# Relay_Cape.net
KiCad netlist of a schematic drawn in EAGLE
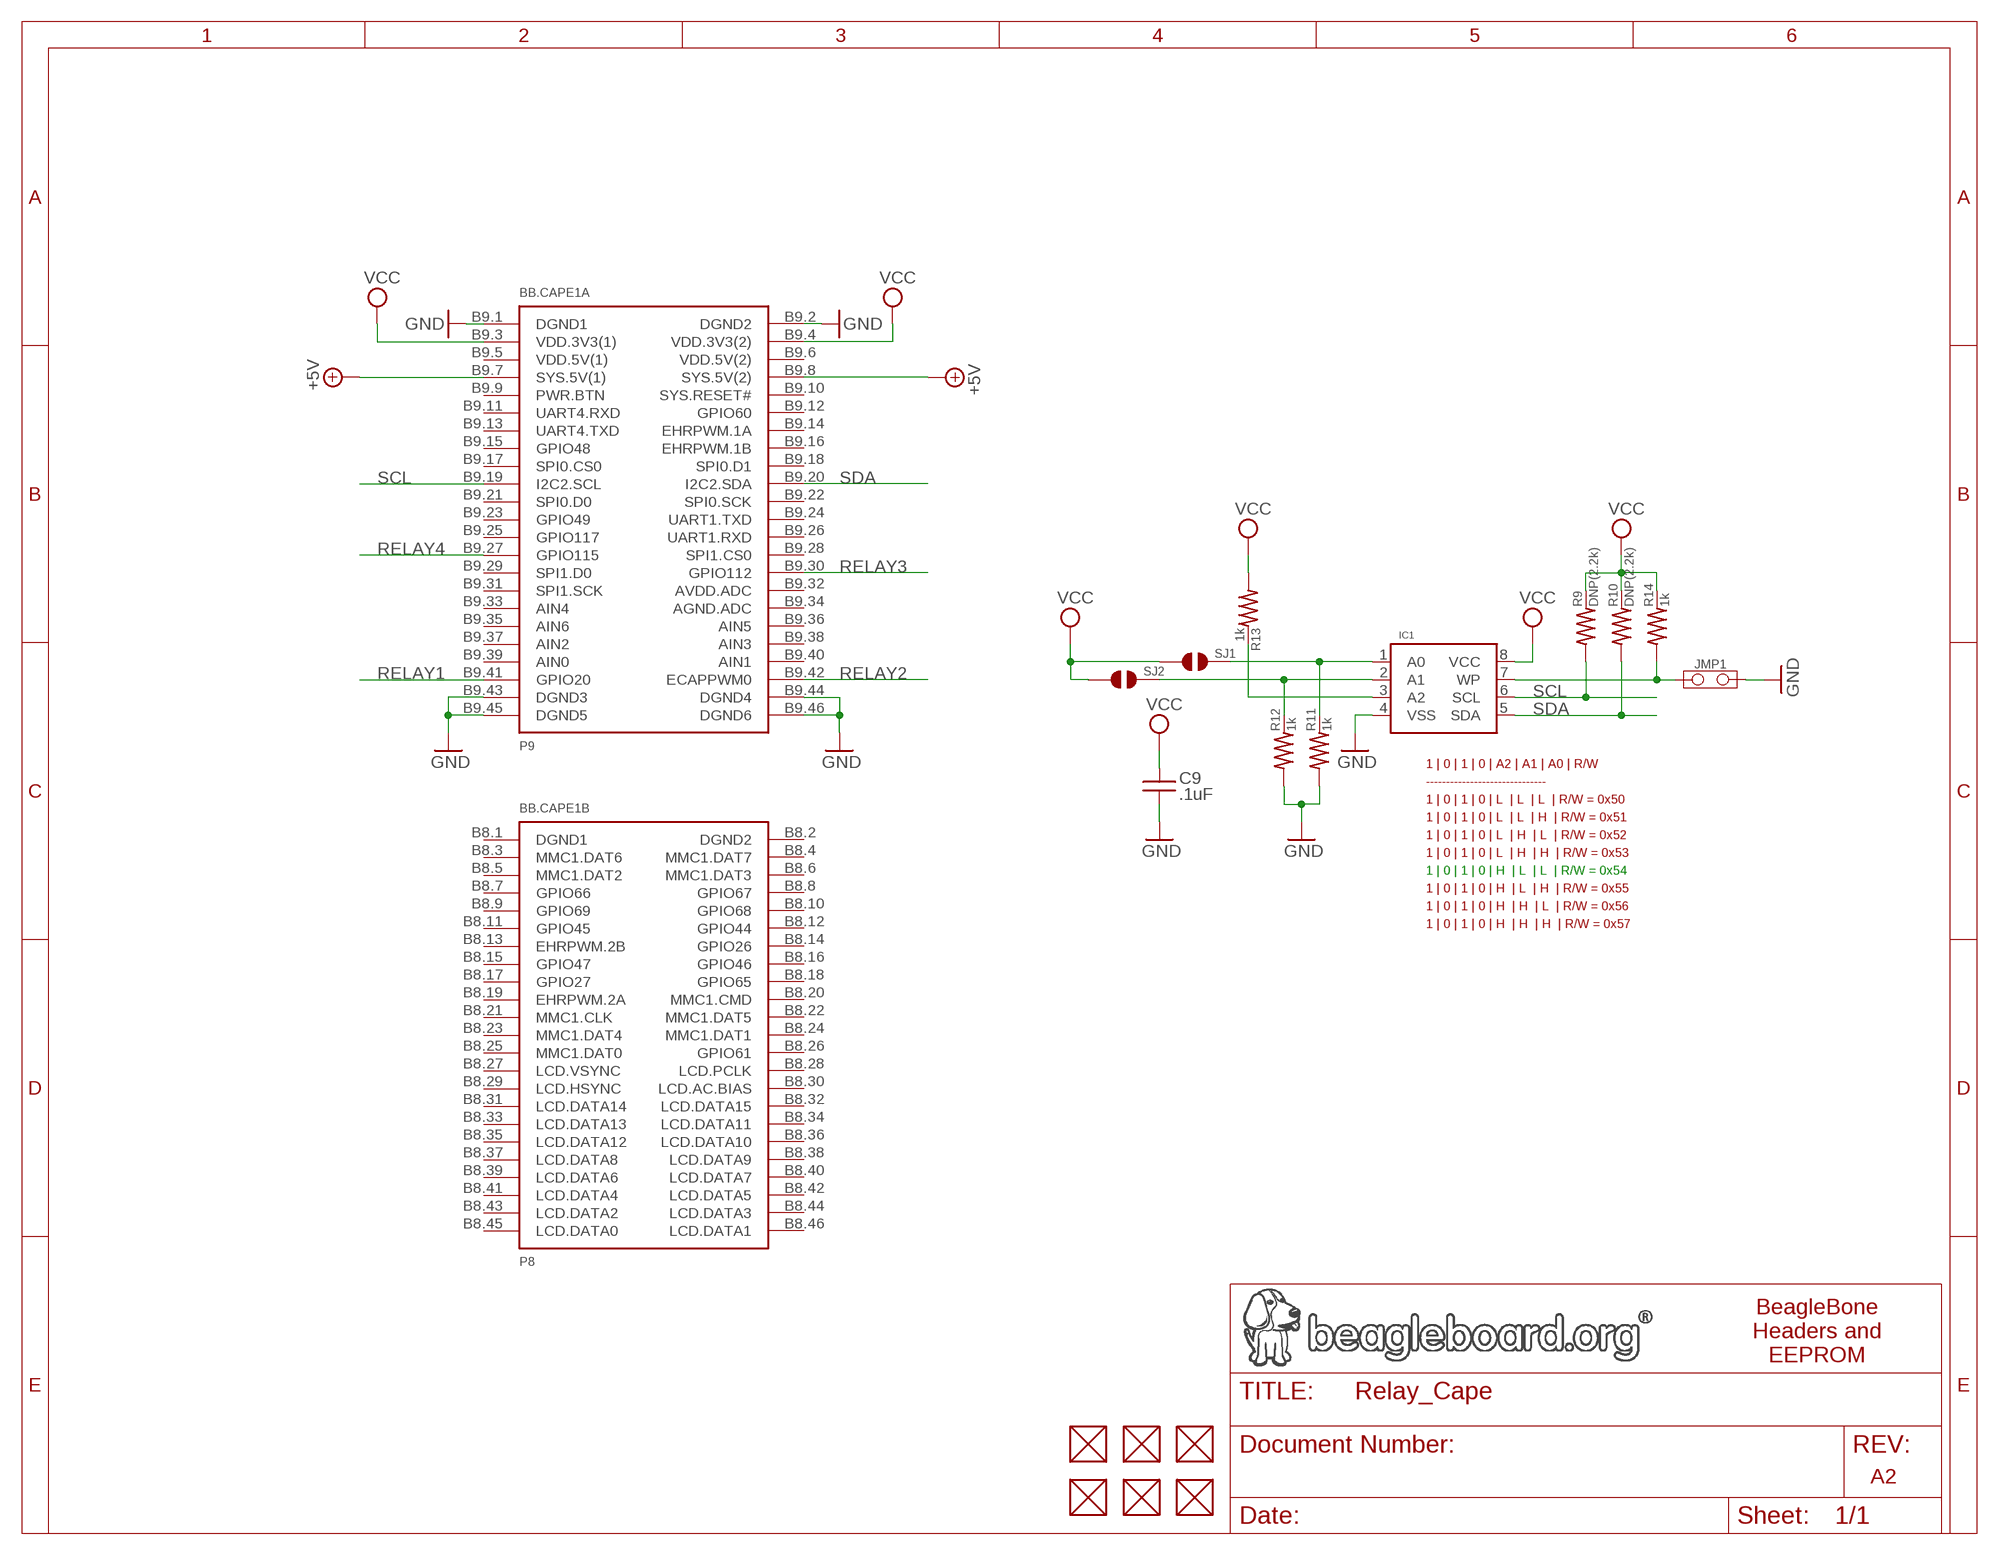
[diagram p0: schematic, sheet 1, part 1 of 2]
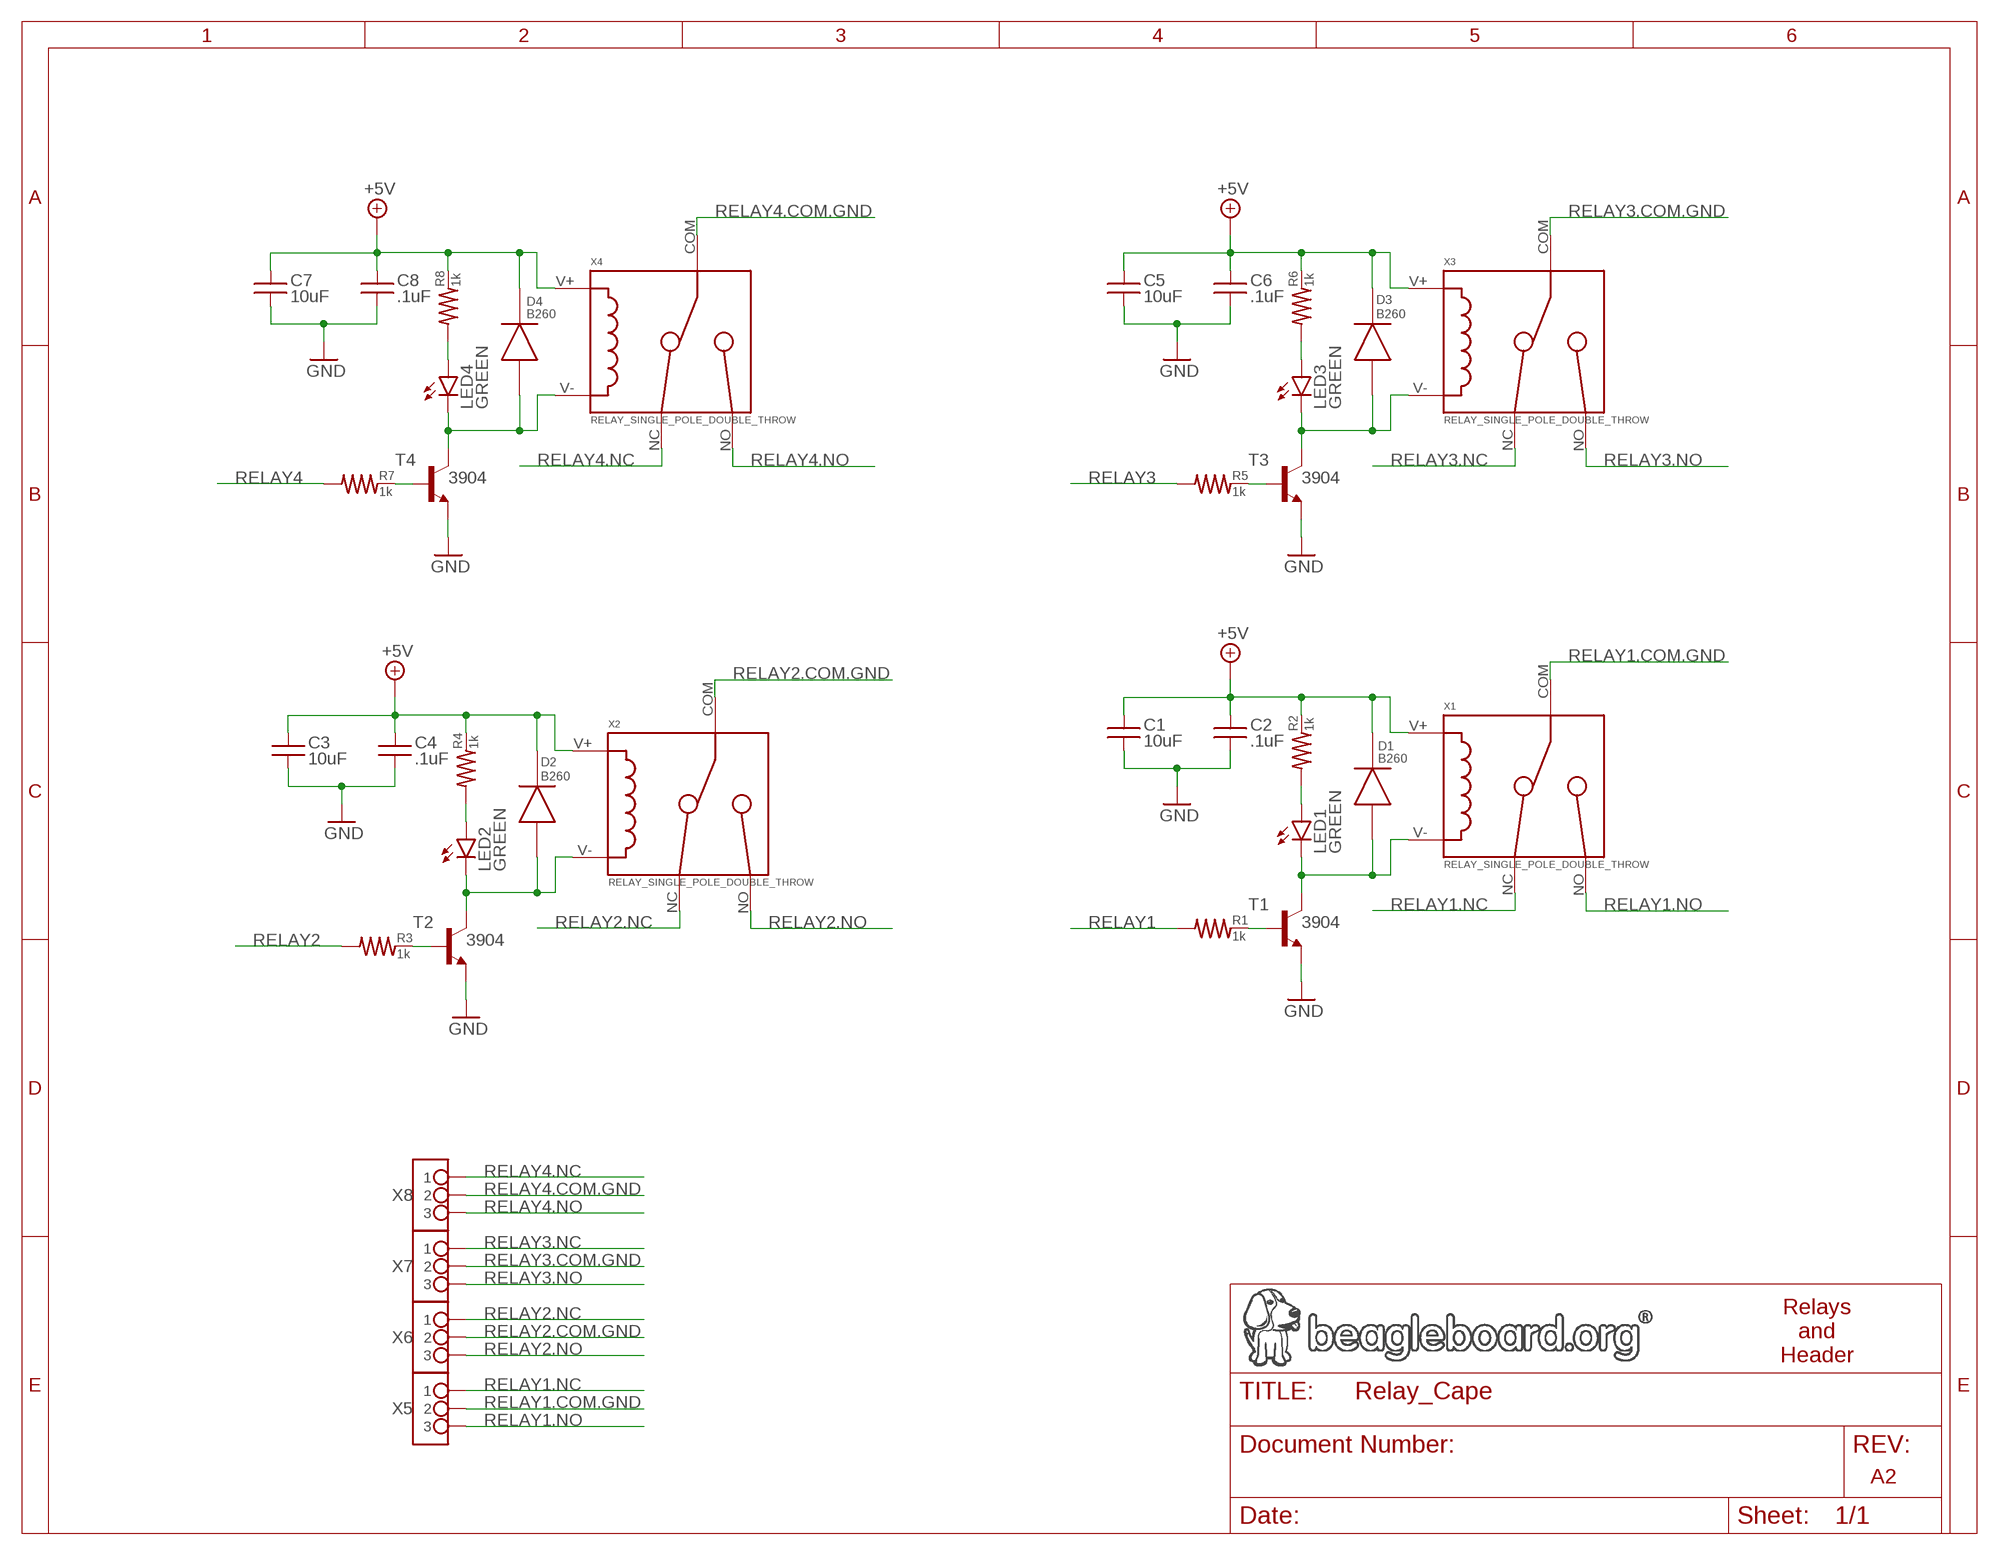
[diagram p1: schematic, sheet 1, part 2 of 2]

(export (version "E")
  (design (tool "Eeschema 10.0.6"))
  (components
    (comp (ref "BB.CAPE1")
      (value "BEAGLEBONE.CAPE.BOTTOM-ONLY-PADS")
      (footprint "eagle-import:BEAGLEBONE.CAPE.BOTTOM-ONLY-PADS")
      (libsource (lib "eagle-import") (part "BEAGLEBONE.CAPE.BOTTOM-ONLY-PADS"))
    )
    (comp (ref "C1")
      (value "10uF")
      (footprint "eagle-import:0805")
      (libsource (lib "eagle-import") (part "CAPACITOR-(INCH)-0805"))
    )
    (comp (ref "C2")
      (value ".1uF")
      (footprint "eagle-import:0402")
      (libsource (lib "eagle-import") (part "CAPACITOR-(INCH)-0402"))
    )
    (comp (ref "C3")
      (value "10uF")
      (footprint "eagle-import:0805")
      (libsource (lib "eagle-import") (part "CAPACITOR-(INCH)-0805"))
    )
    (comp (ref "C4")
      (value ".1uF")
      (footprint "eagle-import:0402")
      (libsource (lib "eagle-import") (part "CAPACITOR-(INCH)-0402"))
    )
    (comp (ref "C5")
      (value "10uF")
      (footprint "eagle-import:0805")
      (libsource (lib "eagle-import") (part "CAPACITOR-(INCH)-0805"))
    )
    (comp (ref "C6")
      (value ".1uF")
      (footprint "eagle-import:0402")
      (libsource (lib "eagle-import") (part "CAPACITOR-(INCH)-0402"))
    )
    (comp (ref "C7")
      (value "10uF")
      (footprint "eagle-import:0805")
      (libsource (lib "eagle-import") (part "CAPACITOR-(INCH)-0805"))
    )
    (comp (ref "C8")
      (value ".1uF")
      (footprint "eagle-import:0402")
      (libsource (lib "eagle-import") (part "CAPACITOR-(INCH)-0402"))
    )
    (comp (ref "C9")
      (value ".1uF")
      (footprint "eagle-import:0402")
      (libsource (lib "eagle-import") (part "CAPACITOR-(INCH)-0402"))
    )
    (comp (ref "D1")
      (value "B260")
      (footprint "eagle-import:DIODE_SMA")
      (libsource (lib "eagle-import") (part "DIODE_SMA"))
    )
    (comp (ref "D2")
      (value "B260")
      (footprint "eagle-import:DIODE_SMA")
      (libsource (lib "eagle-import") (part "DIODE_SMA"))
    )
    (comp (ref "D3")
      (value "B260")
      (footprint "eagle-import:DIODE_SMA")
      (libsource (lib "eagle-import") (part "DIODE_SMA"))
    )
    (comp (ref "D4")
      (value "B260")
      (footprint "eagle-import:DIODE_SMA")
      (libsource (lib "eagle-import") (part "DIODE_SMA"))
    )
    (comp (ref "FUD1")
      (value "FIDUCIAL")
      (footprint "eagle-import:FIDUCIAL_40MIL")
      (libsource (lib "eagle-import") (part "FIDUCIAL"))
    )
    (comp (ref "FUD2")
      (value "FIDUCIAL")
      (footprint "eagle-import:FIDUCIAL_40MIL")
      (libsource (lib "eagle-import") (part "FIDUCIAL"))
    )
    (comp (ref "FUD3")
      (value "FIDUCIAL")
      (footprint "eagle-import:FIDUCIAL_40MIL")
      (libsource (lib "eagle-import") (part "FIDUCIAL"))
    )
    (comp (ref "FUD4")
      (value "FIDUCIAL")
      (footprint "eagle-import:FIDUCIAL_40MIL")
      (libsource (lib "eagle-import") (part "FIDUCIAL"))
    )
    (comp (ref "FUD5")
      (value "FIDUCIAL")
      (footprint "eagle-import:FIDUCIAL_40MIL")
      (libsource (lib "eagle-import") (part "FIDUCIAL"))
    )
    (comp (ref "FUD6")
      (value "FIDUCIAL")
      (footprint "eagle-import:FIDUCIAL_40MIL")
      (libsource (lib "eagle-import") (part "FIDUCIAL"))
    )
    (comp (ref "IC1")
      (value "CAT24C32")
      (footprint "eagle-import:UDFN8,2X3(ON-SEMI)")
      (libsource (lib "eagle-import") (part "CAT24C32"))
    )
    (comp (ref "JMP1")
      (value "JUMPER-(X2)")
      (footprint "eagle-import:JUMPER-(X2)")
      (libsource (lib "eagle-import") (part "JUMPER-(X2)"))
    )
    (comp (ref "LED1")
      (value "GREEN")
      (footprint "eagle-import:0805-LED")
      (libsource (lib "eagle-import") (part "LED-(INCH)-0805"))
    )
    (comp (ref "LED2")
      (value "GREEN")
      (footprint "eagle-import:0805-LED")
      (libsource (lib "eagle-import") (part "LED-(INCH)-0805"))
    )
    (comp (ref "LED3")
      (value "GREEN")
      (footprint "eagle-import:0805-LED")
      (libsource (lib "eagle-import") (part "LED-(INCH)-0805"))
    )
    (comp (ref "LED4")
      (value "GREEN")
      (footprint "eagle-import:0805-LED")
      (libsource (lib "eagle-import") (part "LED-(INCH)-0805"))
    )
    (comp (ref "R1")
      (value "1k")
      (footprint "eagle-import:0402")
      (libsource (lib "eagle-import") (part "RESISTOR-(INCH)-0402"))
    )
    (comp (ref "R2")
      (value "1k")
      (footprint "eagle-import:0402")
      (libsource (lib "eagle-import") (part "RESISTOR-(INCH)-0402"))
    )
    (comp (ref "R3")
      (value "1k")
      (footprint "eagle-import:0402")
      (libsource (lib "eagle-import") (part "RESISTOR-(INCH)-0402"))
    )
    (comp (ref "R4")
      (value "1k")
      (footprint "eagle-import:0402")
      (libsource (lib "eagle-import") (part "RESISTOR-(INCH)-0402"))
    )
    (comp (ref "R5")
      (value "1k")
      (footprint "eagle-import:0402")
      (libsource (lib "eagle-import") (part "RESISTOR-(INCH)-0402"))
    )
    (comp (ref "R6")
      (value "1k")
      (footprint "eagle-import:0402")
      (libsource (lib "eagle-import") (part "RESISTOR-(INCH)-0402"))
    )
    (comp (ref "R7")
      (value "1k")
      (footprint "eagle-import:0402")
      (libsource (lib "eagle-import") (part "RESISTOR-(INCH)-0402"))
    )
    (comp (ref "R8")
      (value "1k")
      (footprint "eagle-import:0402")
      (libsource (lib "eagle-import") (part "RESISTOR-(INCH)-0402"))
    )
    (comp (ref "R9")
      (value "DNP(2.2k)")
      (footprint "eagle-import:0402")
      (libsource (lib "eagle-import") (part "RESISTOR-(INCH)-0402"))
    )
    (comp (ref "R10")
      (value "DNP(2.2k)")
      (footprint "eagle-import:0402")
      (libsource (lib "eagle-import") (part "RESISTOR-(INCH)-0402"))
    )
    (comp (ref "R11")
      (value "1k")
      (footprint "eagle-import:0402")
      (libsource (lib "eagle-import") (part "RESISTOR-(INCH)-0402"))
    )
    (comp (ref "R12")
      (value "1k")
      (footprint "eagle-import:0402")
      (libsource (lib "eagle-import") (part "RESISTOR-(INCH)-0402"))
    )
    (comp (ref "R13")
      (value "1k")
      (footprint "eagle-import:0402")
      (libsource (lib "eagle-import") (part "RESISTOR-(INCH)-0402"))
    )
    (comp (ref "R14")
      (value "1k")
      (footprint "eagle-import:0402")
      (libsource (lib "eagle-import") (part "RESISTOR-(INCH)-0402"))
    )
    (comp (ref "SJ1")
      (value "SOLDER.JOINT-(INCH)-0603")
      (footprint "eagle-import:SOLDER.JOINT(0603)")
      (libsource (lib "eagle-import") (part "SOLDER.JOINT-(INCH)-0603"))
    )
    (comp (ref "SJ2")
      (value "SOLDER.JOINT-(INCH)-0603")
      (footprint "eagle-import:SOLDER.JOINT(0603)")
      (libsource (lib "eagle-import") (part "SOLDER.JOINT-(INCH)-0603"))
    )
    (comp (ref "T1")
      (value "3904")
      (footprint "eagle-import:SOT23-BEC")
      (libsource (lib "eagle-import") (part "-NPN-SOT23-BECBC847"))
    )
    (comp (ref "T2")
      (value "3904")
      (footprint "eagle-import:SOT23-BEC")
      (libsource (lib "eagle-import") (part "-NPN-SOT23-BECBC847"))
    )
    (comp (ref "T3")
      (value "3904")
      (footprint "eagle-import:SOT23-BEC")
      (libsource (lib "eagle-import") (part "-NPN-SOT23-BECBC847"))
    )
    (comp (ref "T4")
      (value "3904")
      (footprint "eagle-import:SOT23-BEC")
      (libsource (lib "eagle-import") (part "-NPN-SOT23-BECBC847"))
    )
    (comp (ref "X1")
      (value "RELAY_SINGLE_POLE_DOUBLE_THROW")
      (footprint "eagle-import:GOODSKY.RWH-SH-105D")
      (libsource (lib "eagle-import") (part "RELAY_SINGLE_POLE_DOUBLE_THROW"))
    )
    (comp (ref "X2")
      (value "RELAY_SINGLE_POLE_DOUBLE_THROW")
      (footprint "eagle-import:GOODSKY.RWH-SH-105D")
      (libsource (lib "eagle-import") (part "RELAY_SINGLE_POLE_DOUBLE_THROW"))
    )
    (comp (ref "X3")
      (value "RELAY_SINGLE_POLE_DOUBLE_THROW")
      (footprint "eagle-import:GOODSKY.RWH-SH-105D")
      (libsource (lib "eagle-import") (part "RELAY_SINGLE_POLE_DOUBLE_THROW"))
    )
    (comp (ref "X4")
      (value "RELAY_SINGLE_POLE_DOUBLE_THROW")
      (footprint "eagle-import:GOODSKY.RWH-SH-105D")
      (libsource (lib "eagle-import") (part "RELAY_SINGLE_POLE_DOUBLE_THROW"))
    )
    (comp (ref "X5")
      (value "TB-3TERM-5MM.PITCH-(50MIL.HOLES)")
      (footprint "eagle-import:TERMINAL.BLOCK-3TERM-5MM.PITCH-(50MIL.HOLES)")
      (libsource (lib "eagle-import") (part "TB-3TERM-5MM.PITCH-(50MIL.HOLES)"))
    )
    (comp (ref "X6")
      (value "TB-3TERM-5MM.PITCH-(50MIL.HOLES)")
      (footprint "eagle-import:TERMINAL.BLOCK-3TERM-5MM.PITCH-(50MIL.HOLES)")
      (libsource (lib "eagle-import") (part "TB-3TERM-5MM.PITCH-(50MIL.HOLES)"))
    )
    (comp (ref "X7")
      (value "TB-3TERM-5MM.PITCH-(50MIL.HOLES)")
      (footprint "eagle-import:TERMINAL.BLOCK-3TERM-5MM.PITCH-(50MIL.HOLES)")
      (libsource (lib "eagle-import") (part "TB-3TERM-5MM.PITCH-(50MIL.HOLES)"))
    )
    (comp (ref "X8")
      (value "TB-3TERM-5MM.PITCH-(50MIL.HOLES)")
      (footprint "eagle-import:TERMINAL.BLOCK-3TERM-5MM.PITCH-(50MIL.HOLES)")
      (libsource (lib "eagle-import") (part "TB-3TERM-5MM.PITCH-(50MIL.HOLES)"))
    )
  )
  (nets
    (net (code "1") (name "+5V") (class "Default")
      (node (ref "BB.CAPE1") (pin "B9.7") (pinfunction "SYS.5V(1)_B9.7") (pintype "bidirectional"))
      (node (ref "BB.CAPE1") (pin "B9.8") (pinfunction "SYS.5V(2)_B9.8") (pintype "bidirectional"))
      (node (ref "C1") (pin "1") (pinfunction "1_1") (pintype "bidirectional"))
      (node (ref "C2") (pin "1") (pinfunction "1_1") (pintype "bidirectional"))
      (node (ref "C3") (pin "1") (pinfunction "1_1") (pintype "bidirectional"))
      (node (ref "C4") (pin "1") (pinfunction "1_1") (pintype "bidirectional"))
      (node (ref "C5") (pin "1") (pinfunction "1_1") (pintype "bidirectional"))
      (node (ref "C6") (pin "1") (pinfunction "1_1") (pintype "bidirectional"))
      (node (ref "C7") (pin "1") (pinfunction "1_1") (pintype "bidirectional"))
      (node (ref "C8") (pin "1") (pinfunction "1_1") (pintype "bidirectional"))
      (node (ref "D1") (pin "K") (pinfunction "K_K") (pintype "bidirectional"))
      (node (ref "D2") (pin "K") (pinfunction "K_K") (pintype "bidirectional"))
      (node (ref "D3") (pin "K") (pinfunction "K_K") (pintype "bidirectional"))
      (node (ref "D4") (pin "K") (pinfunction "K_K") (pintype "bidirectional"))
      (node (ref "R2") (pin "2") (pinfunction "2_2") (pintype "bidirectional"))
      (node (ref "R4") (pin "2") (pinfunction "2_2") (pintype "bidirectional"))
      (node (ref "R6") (pin "2") (pinfunction "2_2") (pintype "bidirectional"))
      (node (ref "R8") (pin "2") (pinfunction "2_2") (pintype "bidirectional"))
      (node (ref "X1") (pin "V+") (pinfunction "V+_V+") (pintype "bidirectional"))
      (node (ref "X2") (pin "V+") (pinfunction "V+_V+") (pintype "bidirectional"))
      (node (ref "X3") (pin "V+") (pinfunction "V+_V+") (pintype "bidirectional"))
      (node (ref "X4") (pin "V+") (pinfunction "V+_V+") (pintype "bidirectional"))
    )
    (net (code "2") (name "/RELAY1") (class "Default")
      (node (ref "BB.CAPE1") (pin "B9.41") (pinfunction "GPIO20_B9.41") (pintype "bidirectional"))
      (node (ref "R1") (pin "1") (pinfunction "1_1") (pintype "bidirectional"))
    )
    (net (code "3") (name "/RELAY1.COM.GND") (class "Default")
      (node (ref "X1") (pin "COM") (pinfunction "COM_COM") (pintype "bidirectional"))
      (node (ref "X5") (pin "2") (pinfunction "2_2") (pintype "bidirectional"))
    )
    (net (code "4") (name "/RELAY1.NC") (class "Default")
      (node (ref "X1") (pin "NC") (pinfunction "NC_NC") (pintype "bidirectional"))
      (node (ref "X5") (pin "1") (pinfunction "1_1") (pintype "bidirectional"))
    )
    (net (code "5") (name "/RELAY1.NO") (class "Default")
      (node (ref "X1") (pin "NO") (pinfunction "NO_NO") (pintype "bidirectional"))
      (node (ref "X5") (pin "3") (pinfunction "3_3") (pintype "bidirectional"))
    )
    (net (code "6") (name "/RELAY2") (class "Default")
      (node (ref "BB.CAPE1") (pin "B9.42") (pinfunction "ECAPPWM0_B9.42") (pintype "bidirectional"))
      (node (ref "R3") (pin "1") (pinfunction "1_1") (pintype "bidirectional"))
    )
    (net (code "7") (name "/RELAY2.COM.GND") (class "Default")
      (node (ref "X2") (pin "COM") (pinfunction "COM_COM") (pintype "bidirectional"))
      (node (ref "X6") (pin "2") (pinfunction "2_2") (pintype "bidirectional"))
    )
    (net (code "8") (name "/RELAY2.NC") (class "Default")
      (node (ref "X2") (pin "NC") (pinfunction "NC_NC") (pintype "bidirectional"))
      (node (ref "X6") (pin "1") (pinfunction "1_1") (pintype "bidirectional"))
    )
    (net (code "9") (name "/RELAY2.NO") (class "Default")
      (node (ref "X2") (pin "NO") (pinfunction "NO_NO") (pintype "bidirectional"))
      (node (ref "X6") (pin "3") (pinfunction "3_3") (pintype "bidirectional"))
    )
    (net (code "10") (name "/RELAY3") (class "Default")
      (node (ref "BB.CAPE1") (pin "B9.30") (pinfunction "GPIO112_B9.30") (pintype "bidirectional"))
      (node (ref "R5") (pin "1") (pinfunction "1_1") (pintype "bidirectional"))
    )
    (net (code "11") (name "/RELAY3.COM.GND") (class "Default")
      (node (ref "X3") (pin "COM") (pinfunction "COM_COM") (pintype "bidirectional"))
      (node (ref "X7") (pin "2") (pinfunction "2_2") (pintype "bidirectional"))
    )
    (net (code "12") (name "/RELAY3.NC") (class "Default")
      (node (ref "X3") (pin "NC") (pinfunction "NC_NC") (pintype "bidirectional"))
      (node (ref "X7") (pin "1") (pinfunction "1_1") (pintype "bidirectional"))
    )
    (net (code "13") (name "/RELAY3.NO") (class "Default")
      (node (ref "X3") (pin "NO") (pinfunction "NO_NO") (pintype "bidirectional"))
      (node (ref "X7") (pin "3") (pinfunction "3_3") (pintype "bidirectional"))
    )
    (net (code "14") (name "/RELAY4") (class "Default")
      (node (ref "BB.CAPE1") (pin "B9.27") (pinfunction "GPIO115_B9.27") (pintype "bidirectional"))
      (node (ref "R7") (pin "1") (pinfunction "1_1") (pintype "bidirectional"))
    )
    (net (code "15") (name "/RELAY4.COM.GND") (class "Default")
      (node (ref "X4") (pin "COM") (pinfunction "COM_COM") (pintype "bidirectional"))
      (node (ref "X8") (pin "2") (pinfunction "2_2") (pintype "bidirectional"))
    )
    (net (code "16") (name "/RELAY4.NC") (class "Default")
      (node (ref "X4") (pin "NC") (pinfunction "NC_NC") (pintype "bidirectional"))
      (node (ref "X8") (pin "1") (pinfunction "1_1") (pintype "bidirectional"))
    )
    (net (code "17") (name "/RELAY4.NO") (class "Default")
      (node (ref "X4") (pin "NO") (pinfunction "NO_NO") (pintype "bidirectional"))
      (node (ref "X8") (pin "3") (pinfunction "3_3") (pintype "bidirectional"))
    )
    (net (code "18") (name "/SCL") (class "Default")
      (node (ref "BB.CAPE1") (pin "B9.19") (pinfunction "I2C2.SCL_B9.19") (pintype "bidirectional"))
      (node (ref "IC1") (pin "6") (pinfunction "SCL_6") (pintype "bidirectional"))
      (node (ref "R9") (pin "1") (pinfunction "1_1") (pintype "bidirectional"))
    )
    (net (code "19") (name "/SDA") (class "Default")
      (node (ref "BB.CAPE1") (pin "B9.20") (pinfunction "I2C2.SDA_B9.20") (pintype "bidirectional"))
      (node (ref "IC1") (pin "5") (pinfunction "SDA_5") (pintype "bidirectional"))
      (node (ref "R10") (pin "1") (pinfunction "1_1") (pintype "bidirectional"))
    )
    (net (code "20") (name "GND") (class "Default")
      (node (ref "BB.CAPE1") (pin "B9.1") (pinfunction "DGND1_B9.1") (pintype "bidirectional"))
      (node (ref "BB.CAPE1") (pin "B9.2") (pinfunction "DGND2_B9.2") (pintype "bidirectional"))
      (node (ref "BB.CAPE1") (pin "B9.43") (pinfunction "DGND3_B9.43") (pintype "bidirectional"))
      (node (ref "BB.CAPE1") (pin "B9.44") (pinfunction "DGND4_B9.44") (pintype "bidirectional"))
      (node (ref "BB.CAPE1") (pin "B9.45") (pinfunction "DGND5_B9.45") (pintype "bidirectional"))
      (node (ref "BB.CAPE1") (pin "B9.46") (pinfunction "DGND6_B9.46") (pintype "bidirectional"))
      (node (ref "C1") (pin "2") (pinfunction "2_2") (pintype "bidirectional"))
      (node (ref "C2") (pin "2") (pinfunction "2_2") (pintype "bidirectional"))
      (node (ref "C3") (pin "2") (pinfunction "2_2") (pintype "bidirectional"))
      (node (ref "C4") (pin "2") (pinfunction "2_2") (pintype "bidirectional"))
      (node (ref "C5") (pin "2") (pinfunction "2_2") (pintype "bidirectional"))
      (node (ref "C6") (pin "2") (pinfunction "2_2") (pintype "bidirectional"))
      (node (ref "C7") (pin "2") (pinfunction "2_2") (pintype "bidirectional"))
      (node (ref "C8") (pin "2") (pinfunction "2_2") (pintype "bidirectional"))
      (node (ref "C9") (pin "2") (pinfunction "2_2") (pintype "bidirectional"))
      (node (ref "IC1") (pin "4") (pinfunction "VSS_4") (pintype "bidirectional"))
      (node (ref "JMP1") (pin "2") (pinfunction "2_2") (pintype "bidirectional"))
      (node (ref "R11") (pin "1") (pinfunction "1_1") (pintype "bidirectional"))
      (node (ref "R12") (pin "1") (pinfunction "1_1") (pintype "bidirectional"))
      (node (ref "T1") (pin "E") (pinfunction "E_E") (pintype "passive"))
      (node (ref "T2") (pin "E") (pinfunction "E_E") (pintype "passive"))
      (node (ref "T3") (pin "E") (pinfunction "E_E") (pintype "passive"))
      (node (ref "T4") (pin "E") (pinfunction "E_E") (pintype "passive"))
    )
    (net (code "21") (name "Net-(D1-PadA)") (class "Default")
      (node (ref "D1") (pin "A") (pinfunction "A_A") (pintype "bidirectional"))
      (node (ref "LED1") (pin "K") (pinfunction "K_K") (pintype "passive"))
      (node (ref "T1") (pin "C") (pinfunction "C_C") (pintype "passive"))
      (node (ref "X1") (pin "V-") (pinfunction "V-_V-") (pintype "bidirectional"))
    )
    (net (code "22") (name "Net-(D2-PadA)") (class "Default")
      (node (ref "D2") (pin "A") (pinfunction "A_A") (pintype "bidirectional"))
      (node (ref "LED2") (pin "K") (pinfunction "K_K") (pintype "passive"))
      (node (ref "T2") (pin "C") (pinfunction "C_C") (pintype "passive"))
      (node (ref "X2") (pin "V-") (pinfunction "V-_V-") (pintype "bidirectional"))
    )
    (net (code "23") (name "Net-(D3-PadA)") (class "Default")
      (node (ref "D3") (pin "A") (pinfunction "A_A") (pintype "bidirectional"))
      (node (ref "LED3") (pin "K") (pinfunction "K_K") (pintype "passive"))
      (node (ref "T3") (pin "C") (pinfunction "C_C") (pintype "passive"))
      (node (ref "X3") (pin "V-") (pinfunction "V-_V-") (pintype "bidirectional"))
    )
    (net (code "24") (name "Net-(D4-PadA)") (class "Default")
      (node (ref "D4") (pin "A") (pinfunction "A_A") (pintype "bidirectional"))
      (node (ref "LED4") (pin "K") (pinfunction "K_K") (pintype "passive"))
      (node (ref "T4") (pin "C") (pinfunction "C_C") (pintype "passive"))
      (node (ref "X4") (pin "V-") (pinfunction "V-_V-") (pintype "bidirectional"))
    )
    (net (code "25") (name "Net-(IC1-A0)") (class "Default")
      (node (ref "IC1") (pin "1") (pinfunction "A0_1") (pintype "bidirectional"))
      (node (ref "R11") (pin "2") (pinfunction "2_2") (pintype "bidirectional"))
      (node (ref "SJ1") (pin "2") (pinfunction "2_2") (pintype "bidirectional"))
    )
    (net (code "26") (name "Net-(IC1-A1)") (class "Default")
      (node (ref "IC1") (pin "2") (pinfunction "A1_2") (pintype "bidirectional"))
      (node (ref "R12") (pin "2") (pinfunction "2_2") (pintype "bidirectional"))
      (node (ref "SJ2") (pin "2") (pinfunction "2_2") (pintype "bidirectional"))
    )
    (net (code "27") (name "Net-(IC1-A2)") (class "Default")
      (node (ref "IC1") (pin "3") (pinfunction "A2_3") (pintype "bidirectional"))
      (node (ref "R13") (pin "2") (pinfunction "2_2") (pintype "bidirectional"))
    )
    (net (code "28") (name "Net-(IC1-WP)") (class "Default")
      (node (ref "IC1") (pin "7") (pinfunction "WP_7") (pintype "bidirectional"))
      (node (ref "JMP1") (pin "1") (pinfunction "1_1") (pintype "bidirectional"))
      (node (ref "R14") (pin "1") (pinfunction "1_1") (pintype "bidirectional"))
    )
    (net (code "29") (name "Net-(LED1-PadA)") (class "Default")
      (node (ref "LED1") (pin "A") (pinfunction "A_A") (pintype "passive"))
      (node (ref "R2") (pin "1") (pinfunction "1_1") (pintype "bidirectional"))
    )
    (net (code "30") (name "Net-(LED2-PadA)") (class "Default")
      (node (ref "LED2") (pin "A") (pinfunction "A_A") (pintype "passive"))
      (node (ref "R4") (pin "1") (pinfunction "1_1") (pintype "bidirectional"))
    )
    (net (code "31") (name "Net-(LED3-PadA)") (class "Default")
      (node (ref "LED3") (pin "A") (pinfunction "A_A") (pintype "passive"))
      (node (ref "R6") (pin "1") (pinfunction "1_1") (pintype "bidirectional"))
    )
    (net (code "32") (name "Net-(LED4-PadA)") (class "Default")
      (node (ref "LED4") (pin "A") (pinfunction "A_A") (pintype "passive"))
      (node (ref "R8") (pin "1") (pinfunction "1_1") (pintype "bidirectional"))
    )
    (net (code "33") (name "Net-(R1-Pad2)") (class "Default")
      (node (ref "R1") (pin "2") (pinfunction "2_2") (pintype "bidirectional"))
      (node (ref "T1") (pin "B") (pinfunction "B_B") (pintype "passive"))
    )
    (net (code "34") (name "Net-(R3-Pad2)") (class "Default")
      (node (ref "R3") (pin "2") (pinfunction "2_2") (pintype "bidirectional"))
      (node (ref "T2") (pin "B") (pinfunction "B_B") (pintype "passive"))
    )
    (net (code "35") (name "Net-(R5-Pad2)") (class "Default")
      (node (ref "R5") (pin "2") (pinfunction "2_2") (pintype "bidirectional"))
      (node (ref "T3") (pin "B") (pinfunction "B_B") (pintype "passive"))
    )
    (net (code "36") (name "Net-(R7-Pad2)") (class "Default")
      (node (ref "R7") (pin "2") (pinfunction "2_2") (pintype "bidirectional"))
      (node (ref "T4") (pin "B") (pinfunction "B_B") (pintype "passive"))
    )
    (net (code "37") (name "VCC") (class "Default")
      (node (ref "BB.CAPE1") (pin "B9.3") (pinfunction "VDD.3V3(1)_B9.3") (pintype "bidirectional"))
      (node (ref "BB.CAPE1") (pin "B9.4") (pinfunction "VDD.3V3(2)_B9.4") (pintype "bidirectional"))
      (node (ref "C9") (pin "1") (pinfunction "1_1") (pintype "bidirectional"))
      (node (ref "IC1") (pin "8") (pinfunction "VCC_8") (pintype "bidirectional"))
      (node (ref "R10") (pin "2") (pinfunction "2_2") (pintype "bidirectional"))
      (node (ref "R13") (pin "1") (pinfunction "1_1") (pintype "bidirectional"))
      (node (ref "R14") (pin "2") (pinfunction "2_2") (pintype "bidirectional"))
      (node (ref "R9") (pin "2") (pinfunction "2_2") (pintype "bidirectional"))
      (node (ref "SJ1") (pin "1") (pinfunction "1_1") (pintype "bidirectional"))
      (node (ref "SJ2") (pin "1") (pinfunction "1_1") (pintype "bidirectional"))
    )
    (net (code "38") (name "unconnected-(BB.CAPE1A-AGND.ADC-PadB9.34)") (class "Default")
      (node (ref "BB.CAPE1") (pin "B9.34") (pinfunction "AGND.ADC_B9.34") (pintype "bidirectional"))
    )
    (net (code "39") (name "unconnected-(BB.CAPE1A-AIN0-PadB9.39)") (class "Default")
      (node (ref "BB.CAPE1") (pin "B9.39") (pinfunction "AIN0_B9.39") (pintype "bidirectional"))
    )
    (net (code "40") (name "unconnected-(BB.CAPE1A-AIN1-PadB9.40)") (class "Default")
      (node (ref "BB.CAPE1") (pin "B9.40") (pinfunction "AIN1_B9.40") (pintype "bidirectional"))
    )
    (net (code "41") (name "unconnected-(BB.CAPE1A-AIN2-PadB9.37)") (class "Default")
      (node (ref "BB.CAPE1") (pin "B9.37") (pinfunction "AIN2_B9.37") (pintype "bidirectional"))
    )
    (net (code "42") (name "unconnected-(BB.CAPE1A-AIN3-PadB9.38)") (class "Default")
      (node (ref "BB.CAPE1") (pin "B9.38") (pinfunction "AIN3_B9.38") (pintype "bidirectional"))
    )
    (net (code "43") (name "unconnected-(BB.CAPE1A-AIN4-PadB9.33)") (class "Default")
      (node (ref "BB.CAPE1") (pin "B9.33") (pinfunction "AIN4_B9.33") (pintype "bidirectional"))
    )
    (net (code "44") (name "unconnected-(BB.CAPE1A-AIN5-PadB9.36)") (class "Default")
      (node (ref "BB.CAPE1") (pin "B9.36") (pinfunction "AIN5_B9.36") (pintype "bidirectional"))
    )
    (net (code "45") (name "unconnected-(BB.CAPE1A-AIN6-PadB9.35)") (class "Default")
      (node (ref "BB.CAPE1") (pin "B9.35") (pinfunction "AIN6_B9.35") (pintype "bidirectional"))
    )
    (net (code "46") (name "unconnected-(BB.CAPE1A-AVDD.ADC-PadB9.32)") (class "Default")
      (node (ref "BB.CAPE1") (pin "B9.32") (pinfunction "AVDD.ADC_B9.32") (pintype "bidirectional"))
    )
    (net (code "47") (name "unconnected-(BB.CAPE1A-EHRPWM.1A-PadB9.14)") (class "Default")
      (node (ref "BB.CAPE1") (pin "B9.14") (pinfunction "EHRPWM.1A_B9.14") (pintype "bidirectional"))
    )
    (net (code "48") (name "unconnected-(BB.CAPE1A-EHRPWM.1B-PadB9.16)") (class "Default")
      (node (ref "BB.CAPE1") (pin "B9.16") (pinfunction "EHRPWM.1B_B9.16") (pintype "bidirectional"))
    )
    (net (code "49") (name "unconnected-(BB.CAPE1A-GPIO48-PadB9.15)") (class "Default")
      (node (ref "BB.CAPE1") (pin "B9.15") (pinfunction "GPIO48_B9.15") (pintype "bidirectional"))
    )
    (net (code "50") (name "unconnected-(BB.CAPE1A-GPIO49-PadB9.23)") (class "Default")
      (node (ref "BB.CAPE1") (pin "B9.23") (pinfunction "GPIO49_B9.23") (pintype "bidirectional"))
    )
    (net (code "51") (name "unconnected-(BB.CAPE1A-GPIO60-PadB9.12)") (class "Default")
      (node (ref "BB.CAPE1") (pin "B9.12") (pinfunction "GPIO60_B9.12") (pintype "bidirectional"))
    )
    (net (code "52") (name "unconnected-(BB.CAPE1A-GPIO117-PadB9.25)") (class "Default")
      (node (ref "BB.CAPE1") (pin "B9.25") (pinfunction "GPIO117_B9.25") (pintype "bidirectional"))
    )
    (net (code "53") (name "unconnected-(BB.CAPE1A-PWR.BTN-PadB9.9)") (class "Default")
      (node (ref "BB.CAPE1") (pin "B9.9") (pinfunction "PWR.BTN_B9.9") (pintype "bidirectional"))
    )
    (net (code "54") (name "unconnected-(BB.CAPE1A-SPI0.CS0-PadB9.17)") (class "Default")
      (node (ref "BB.CAPE1") (pin "B9.17") (pinfunction "SPI0.CS0_B9.17") (pintype "bidirectional"))
    )
    (net (code "55") (name "unconnected-(BB.CAPE1A-SPI0.D0-PadB9.21)") (class "Default")
      (node (ref "BB.CAPE1") (pin "B9.21") (pinfunction "SPI0.D0_B9.21") (pintype "bidirectional"))
    )
    (net (code "56") (name "unconnected-(BB.CAPE1A-SPI0.D1-PadB9.18)") (class "Default")
      (node (ref "BB.CAPE1") (pin "B9.18") (pinfunction "SPI0.D1_B9.18") (pintype "bidirectional"))
    )
    (net (code "57") (name "unconnected-(BB.CAPE1A-SPI0.SCK-PadB9.22)") (class "Default")
      (node (ref "BB.CAPE1") (pin "B9.22") (pinfunction "SPI0.SCK_B9.22") (pintype "bidirectional"))
    )
    (net (code "58") (name "unconnected-(BB.CAPE1A-SPI1.CS0-PadB9.28)") (class "Default")
      (node (ref "BB.CAPE1") (pin "B9.28") (pinfunction "SPI1.CS0_B9.28") (pintype "bidirectional"))
    )
    (net (code "59") (name "unconnected-(BB.CAPE1A-SPI1.D0-PadB9.29)") (class "Default")
      (node (ref "BB.CAPE1") (pin "B9.29") (pinfunction "SPI1.D0_B9.29") (pintype "bidirectional"))
    )
    (net (code "60") (name "unconnected-(BB.CAPE1A-SPI1.SCK-PadB9.31)") (class "Default")
      (node (ref "BB.CAPE1") (pin "B9.31") (pinfunction "SPI1.SCK_B9.31") (pintype "bidirectional"))
    )
    (net (code "61") (name "unconnected-(BB.CAPE1A-SYS.RESET#-PadB9.10)") (class "Default")
      (node (ref "BB.CAPE1") (pin "B9.10") (pinfunction "SYS.RESET#_B9.10") (pintype "bidirectional"))
    )
    (net (code "62") (name "unconnected-(BB.CAPE1A-UART1.RXD-PadB9.26)") (class "Default")
      (node (ref "BB.CAPE1") (pin "B9.26") (pinfunction "UART1.RXD_B9.26") (pintype "bidirectional"))
    )
    (net (code "63") (name "unconnected-(BB.CAPE1A-UART1.TXD-PadB9.24)") (class "Default")
      (node (ref "BB.CAPE1") (pin "B9.24") (pinfunction "UART1.TXD_B9.24") (pintype "bidirectional"))
    )
    (net (code "64") (name "unconnected-(BB.CAPE1A-UART4.RXD-PadB9.11)") (class "Default")
      (node (ref "BB.CAPE1") (pin "B9.11") (pinfunction "UART4.RXD_B9.11") (pintype "bidirectional"))
    )
    (net (code "65") (name "unconnected-(BB.CAPE1A-UART4.TXD-PadB9.13)") (class "Default")
      (node (ref "BB.CAPE1") (pin "B9.13") (pinfunction "UART4.TXD_B9.13") (pintype "bidirectional"))
    )
    (net (code "66") (name "unconnected-(BB.CAPE1A-VDD.5V(1)-PadB9.5)") (class "Default")
      (node (ref "BB.CAPE1") (pin "B9.5") (pinfunction "VDD.5V(1)_B9.5") (pintype "bidirectional"))
    )
    (net (code "67") (name "unconnected-(BB.CAPE1A-VDD.5V(2)-PadB9.6)") (class "Default")
      (node (ref "BB.CAPE1") (pin "B9.6") (pinfunction "VDD.5V(2)_B9.6") (pintype "bidirectional"))
    )
    (net (code "68") (name "unconnected-(BB.CAPE1B-DGND1-PadB8.1)") (class "Default")
      (node (ref "BB.CAPE1") (pin "B8.1") (pinfunction "DGND1_B8.1") (pintype "bidirectional"))
    )
    (net (code "69") (name "unconnected-(BB.CAPE1B-DGND2-PadB8.2)") (class "Default")
      (node (ref "BB.CAPE1") (pin "B8.2") (pinfunction "DGND2_B8.2") (pintype "bidirectional"))
    )
    (net (code "70") (name "unconnected-(BB.CAPE1B-EHRPWM.2A-PadB8.19)") (class "Default")
      (node (ref "BB.CAPE1") (pin "B8.19") (pinfunction "EHRPWM.2A_B8.19") (pintype "bidirectional"))
    )
    (net (code "71") (name "unconnected-(BB.CAPE1B-EHRPWM.2B-PadB8.13)") (class "Default")
      (node (ref "BB.CAPE1") (pin "B8.13") (pinfunction "EHRPWM.2B_B8.13") (pintype "bidirectional"))
    )
    (net (code "72") (name "unconnected-(BB.CAPE1B-GPIO26-PadB8.14)") (class "Default")
      (node (ref "BB.CAPE1") (pin "B8.14") (pinfunction "GPIO26_B8.14") (pintype "bidirectional"))
    )
    (net (code "73") (name "unconnected-(BB.CAPE1B-GPIO27-PadB8.17)") (class "Default")
      (node (ref "BB.CAPE1") (pin "B8.17") (pinfunction "GPIO27_B8.17") (pintype "bidirectional"))
    )
    (net (code "74") (name "unconnected-(BB.CAPE1B-GPIO44-PadB8.12)") (class "Default")
      (node (ref "BB.CAPE1") (pin "B8.12") (pinfunction "GPIO44_B8.12") (pintype "bidirectional"))
    )
    (net (code "75") (name "unconnected-(BB.CAPE1B-GPIO45-PadB8.11)") (class "Default")
      (node (ref "BB.CAPE1") (pin "B8.11") (pinfunction "GPIO45_B8.11") (pintype "bidirectional"))
    )
    (net (code "76") (name "unconnected-(BB.CAPE1B-GPIO46-PadB8.16)") (class "Default")
      (node (ref "BB.CAPE1") (pin "B8.16") (pinfunction "GPIO46_B8.16") (pintype "bidirectional"))
    )
    (net (code "77") (name "unconnected-(BB.CAPE1B-GPIO47-PadB8.15)") (class "Default")
      (node (ref "BB.CAPE1") (pin "B8.15") (pinfunction "GPIO47_B8.15") (pintype "bidirectional"))
    )
    (net (code "78") (name "unconnected-(BB.CAPE1B-GPIO61-PadB8.26)") (class "Default")
      (node (ref "BB.CAPE1") (pin "B8.26") (pinfunction "GPIO61_B8.26") (pintype "bidirectional"))
    )
    (net (code "79") (name "unconnected-(BB.CAPE1B-GPIO65-PadB8.18)") (class "Default")
      (node (ref "BB.CAPE1") (pin "B8.18") (pinfunction "GPIO65_B8.18") (pintype "bidirectional"))
    )
    (net (code "80") (name "unconnected-(BB.CAPE1B-GPIO66-PadB8.7)") (class "Default")
      (node (ref "BB.CAPE1") (pin "B8.7") (pinfunction "GPIO66_B8.7") (pintype "bidirectional"))
    )
    (net (code "81") (name "unconnected-(BB.CAPE1B-GPIO67-PadB8.8)") (class "Default")
      (node (ref "BB.CAPE1") (pin "B8.8") (pinfunction "GPIO67_B8.8") (pintype "bidirectional"))
    )
    (net (code "82") (name "unconnected-(BB.CAPE1B-GPIO68-PadB8.10)") (class "Default")
      (node (ref "BB.CAPE1") (pin "B8.10") (pinfunction "GPIO68_B8.10") (pintype "bidirectional"))
    )
    (net (code "83") (name "unconnected-(BB.CAPE1B-GPIO69-PadB8.9)") (class "Default")
      (node (ref "BB.CAPE1") (pin "B8.9") (pinfunction "GPIO69_B8.9") (pintype "bidirectional"))
    )
    (net (code "84") (name "unconnected-(BB.CAPE1B-LCD.AC.BIAS-PadB8.30)") (class "Default")
      (node (ref "BB.CAPE1") (pin "B8.30") (pinfunction "LCD.AC.BIAS_B8.30") (pintype "bidirectional"))
    )
    (net (code "85") (name "unconnected-(BB.CAPE1B-LCD.DATA0-PadB8.45)") (class "Default")
      (node (ref "BB.CAPE1") (pin "B8.45") (pinfunction "LCD.DATA0_B8.45") (pintype "bidirectional"))
    )
    (net (code "86") (name "unconnected-(BB.CAPE1B-LCD.DATA1-PadB8.46)") (class "Default")
      (node (ref "BB.CAPE1") (pin "B8.46") (pinfunction "LCD.DATA1_B8.46") (pintype "bidirectional"))
    )
    (net (code "87") (name "unconnected-(BB.CAPE1B-LCD.DATA2-PadB8.43)") (class "Default")
      (node (ref "BB.CAPE1") (pin "B8.43") (pinfunction "LCD.DATA2_B8.43") (pintype "bidirectional"))
    )
    (net (code "88") (name "unconnected-(BB.CAPE1B-LCD.DATA3-PadB8.44)") (class "Default")
      (node (ref "BB.CAPE1") (pin "B8.44") (pinfunction "LCD.DATA3_B8.44") (pintype "bidirectional"))
    )
    (net (code "89") (name "unconnected-(BB.CAPE1B-LCD.DATA4-PadB8.41)") (class "Default")
      (node (ref "BB.CAPE1") (pin "B8.41") (pinfunction "LCD.DATA4_B8.41") (pintype "bidirectional"))
    )
    (net (code "90") (name "unconnected-(BB.CAPE1B-LCD.DATA5-PadB8.42)") (class "Default")
      (node (ref "BB.CAPE1") (pin "B8.42") (pinfunction "LCD.DATA5_B8.42") (pintype "bidirectional"))
    )
    (net (code "91") (name "unconnected-(BB.CAPE1B-LCD.DATA6-PadB8.39)") (class "Default")
      (node (ref "BB.CAPE1") (pin "B8.39") (pinfunction "LCD.DATA6_B8.39") (pintype "bidirectional"))
    )
    (net (code "92") (name "unconnected-(BB.CAPE1B-LCD.DATA7-PadB8.40)") (class "Default")
      (node (ref "BB.CAPE1") (pin "B8.40") (pinfunction "LCD.DATA7_B8.40") (pintype "bidirectional"))
    )
    (net (code "93") (name "unconnected-(BB.CAPE1B-LCD.DATA8-PadB8.37)") (class "Default")
      (node (ref "BB.CAPE1") (pin "B8.37") (pinfunction "LCD.DATA8_B8.37") (pintype "bidirectional"))
    )
    (net (code "94") (name "unconnected-(BB.CAPE1B-LCD.DATA9-PadB8.38)") (class "Default")
      (node (ref "BB.CAPE1") (pin "B8.38") (pinfunction "LCD.DATA9_B8.38") (pintype "bidirectional"))
    )
    (net (code "95") (name "unconnected-(BB.CAPE1B-LCD.DATA10-PadB8.36)") (class "Default")
      (node (ref "BB.CAPE1") (pin "B8.36") (pinfunction "LCD.DATA10_B8.36") (pintype "bidirectional"))
    )
    (net (code "96") (name "unconnected-(BB.CAPE1B-LCD.DATA11-PadB8.34)") (class "Default")
      (node (ref "BB.CAPE1") (pin "B8.34") (pinfunction "LCD.DATA11_B8.34") (pintype "bidirectional"))
    )
    (net (code "97") (name "unconnected-(BB.CAPE1B-LCD.DATA12-PadB8.35)") (class "Default")
      (node (ref "BB.CAPE1") (pin "B8.35") (pinfunction "LCD.DATA12_B8.35") (pintype "bidirectional"))
    )
    (net (code "98") (name "unconnected-(BB.CAPE1B-LCD.DATA13-PadB8.33)") (class "Default")
      (node (ref "BB.CAPE1") (pin "B8.33") (pinfunction "LCD.DATA13_B8.33") (pintype "bidirectional"))
    )
    (net (code "99") (name "unconnected-(BB.CAPE1B-LCD.DATA14-PadB8.31)") (class "Default")
      (node (ref "BB.CAPE1") (pin "B8.31") (pinfunction "LCD.DATA14_B8.31") (pintype "bidirectional"))
    )
    (net (code "100") (name "unconnected-(BB.CAPE1B-LCD.DATA15-PadB8.32)") (class "Default")
      (node (ref "BB.CAPE1") (pin "B8.32") (pinfunction "LCD.DATA15_B8.32") (pintype "bidirectional"))
    )
    (net (code "101") (name "unconnected-(BB.CAPE1B-LCD.HSYNC-PadB8.29)") (class "Default")
      (node (ref "BB.CAPE1") (pin "B8.29") (pinfunction "LCD.HSYNC_B8.29") (pintype "bidirectional"))
    )
    (net (code "102") (name "unconnected-(BB.CAPE1B-LCD.PCLK-PadB8.28)") (class "Default")
      (node (ref "BB.CAPE1") (pin "B8.28") (pinfunction "LCD.PCLK_B8.28") (pintype "bidirectional"))
    )
    (net (code "103") (name "unconnected-(BB.CAPE1B-LCD.VSYNC-PadB8.27)") (class "Default")
      (node (ref "BB.CAPE1") (pin "B8.27") (pinfunction "LCD.VSYNC_B8.27") (pintype "bidirectional"))
    )
    (net (code "104") (name "unconnected-(BB.CAPE1B-MMC1.CLK-PadB8.21)") (class "Default")
      (node (ref "BB.CAPE1") (pin "B8.21") (pinfunction "MMC1.CLK_B8.21") (pintype "bidirectional"))
    )
    (net (code "105") (name "unconnected-(BB.CAPE1B-MMC1.CMD-PadB8.20)") (class "Default")
      (node (ref "BB.CAPE1") (pin "B8.20") (pinfunction "MMC1.CMD_B8.20") (pintype "bidirectional"))
    )
    (net (code "106") (name "unconnected-(BB.CAPE1B-MMC1.DAT0-PadB8.25)") (class "Default")
      (node (ref "BB.CAPE1") (pin "B8.25") (pinfunction "MMC1.DAT0_B8.25") (pintype "bidirectional"))
    )
    (net (code "107") (name "unconnected-(BB.CAPE1B-MMC1.DAT1-PadB8.24)") (class "Default")
      (node (ref "BB.CAPE1") (pin "B8.24") (pinfunction "MMC1.DAT1_B8.24") (pintype "bidirectional"))
    )
    (net (code "108") (name "unconnected-(BB.CAPE1B-MMC1.DAT2-PadB8.5)") (class "Default")
      (node (ref "BB.CAPE1") (pin "B8.5") (pinfunction "MMC1.DAT2_B8.5") (pintype "bidirectional"))
    )
    (net (code "109") (name "unconnected-(BB.CAPE1B-MMC1.DAT3-PadB8.6)") (class "Default")
      (node (ref "BB.CAPE1") (pin "B8.6") (pinfunction "MMC1.DAT3_B8.6") (pintype "bidirectional"))
    )
    (net (code "110") (name "unconnected-(BB.CAPE1B-MMC1.DAT4-PadB8.23)") (class "Default")
      (node (ref "BB.CAPE1") (pin "B8.23") (pinfunction "MMC1.DAT4_B8.23") (pintype "bidirectional"))
    )
    (net (code "111") (name "unconnected-(BB.CAPE1B-MMC1.DAT5-PadB8.22)") (class "Default")
      (node (ref "BB.CAPE1") (pin "B8.22") (pinfunction "MMC1.DAT5_B8.22") (pintype "bidirectional"))
    )
    (net (code "112") (name "unconnected-(BB.CAPE1B-MMC1.DAT6-PadB8.3)") (class "Default")
      (node (ref "BB.CAPE1") (pin "B8.3") (pinfunction "MMC1.DAT6_B8.3") (pintype "bidirectional"))
    )
    (net (code "113") (name "unconnected-(BB.CAPE1B-MMC1.DAT7-PadB8.4)") (class "Default")
      (node (ref "BB.CAPE1") (pin "B8.4") (pinfunction "MMC1.DAT7_B8.4") (pintype "bidirectional"))
    )
    (net (code "114") (name "unconnected-(FUD1-PadP$1)") (class "Default")
      (node (ref "FUD1") (pin "P$1") (pinfunction "P$1_P$1") (pintype "no_connect"))
    )
    (net (code "115") (name "unconnected-(FUD2-PadP$1)") (class "Default")
      (node (ref "FUD2") (pin "P$1") (pinfunction "P$1_P$1") (pintype "no_connect"))
    )
    (net (code "116") (name "unconnected-(FUD3-PadP$1)") (class "Default")
      (node (ref "FUD3") (pin "P$1") (pinfunction "P$1_P$1") (pintype "no_connect"))
    )
    (net (code "117") (name "unconnected-(FUD4-PadP$1)") (class "Default")
      (node (ref "FUD4") (pin "P$1") (pinfunction "P$1_P$1") (pintype "no_connect"))
    )
    (net (code "118") (name "unconnected-(FUD5-PadP$1)") (class "Default")
      (node (ref "FUD5") (pin "P$1") (pinfunction "P$1_P$1") (pintype "no_connect"))
    )
    (net (code "119") (name "unconnected-(FUD6-PadP$1)") (class "Default")
      (node (ref "FUD6") (pin "P$1") (pinfunction "P$1_P$1") (pintype "no_connect"))
    )
  )
)
